# sinclair_keyboard_v2.net
KiCad netlist of a schematic drawn in EAGLE
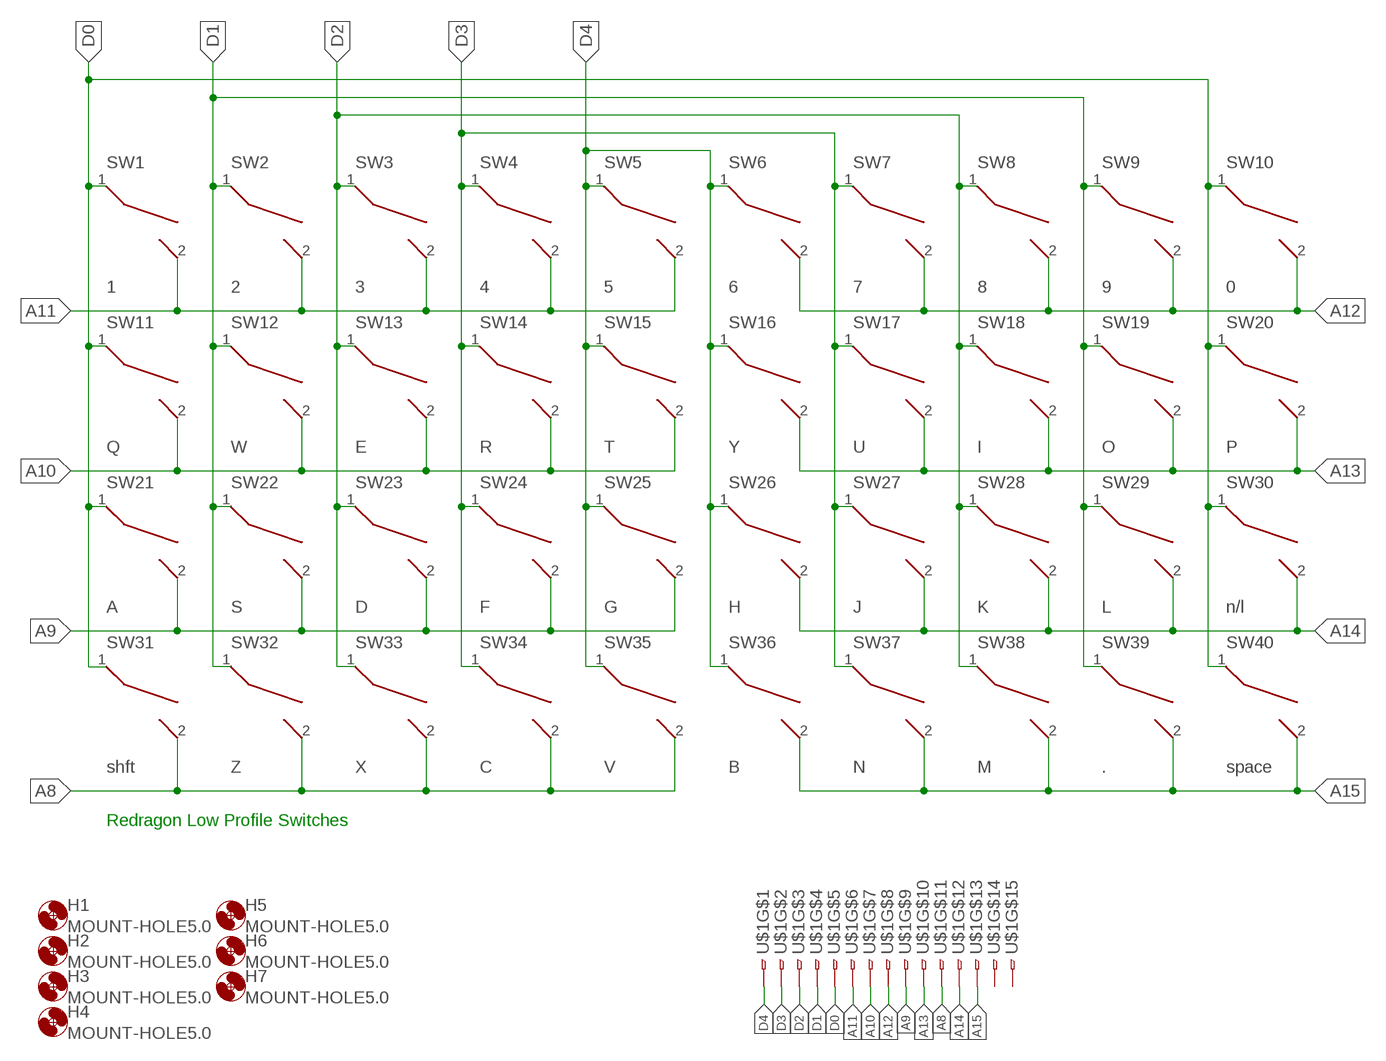
[diagram p0: schematic, sheet 1]

(export (version "E")
  (design (tool "Eeschema 10.0.6"))
  (components
    (comp (ref "H1")
      (value "MOUNT-HOLE5.0")
      (footprint "eagle-import:5,0")
      (libsource (lib "eagle-import") (part "MOUNT-HOLE5.0"))
    )
    (comp (ref "H2")
      (value "MOUNT-HOLE5.0")
      (footprint "eagle-import:5,0")
      (libsource (lib "eagle-import") (part "MOUNT-HOLE5.0"))
    )
    (comp (ref "H3")
      (value "MOUNT-HOLE5.0")
      (footprint "eagle-import:5,0")
      (libsource (lib "eagle-import") (part "MOUNT-HOLE5.0"))
    )
    (comp (ref "H4")
      (value "MOUNT-HOLE5.0")
      (footprint "eagle-import:5,0")
      (libsource (lib "eagle-import") (part "MOUNT-HOLE5.0"))
    )
    (comp (ref "H5")
      (value "MOUNT-HOLE5.0")
      (footprint "eagle-import:5,0")
      (libsource (lib "eagle-import") (part "MOUNT-HOLE5.0"))
    )
    (comp (ref "H6")
      (value "MOUNT-HOLE5.0")
      (footprint "eagle-import:5,0")
      (libsource (lib "eagle-import") (part "MOUNT-HOLE5.0"))
    )
    (comp (ref "H7")
      (value "MOUNT-HOLE5.0")
      (footprint "eagle-import:5,0")
      (libsource (lib "eagle-import") (part "MOUNT-HOLE5.0"))
    )
    (comp (ref "SW1")
      (value "1")
      (footprint "eagle-import:REDRAGON_LOWPROFILE")
      (libsource (lib "eagle-import") (part "CHERRY_MXREDRAGON"))
    )
    (comp (ref "SW2")
      (value "2")
      (footprint "eagle-import:REDRAGON_LOWPROFILE")
      (libsource (lib "eagle-import") (part "CHERRY_MXREDRAGON"))
    )
    (comp (ref "SW3")
      (value "3")
      (footprint "eagle-import:REDRAGON_LOWPROFILE")
      (libsource (lib "eagle-import") (part "CHERRY_MXREDRAGON"))
    )
    (comp (ref "SW4")
      (value "4")
      (footprint "eagle-import:REDRAGON_LOWPROFILE")
      (libsource (lib "eagle-import") (part "CHERRY_MXREDRAGON"))
    )
    (comp (ref "SW5")
      (value "5")
      (footprint "eagle-import:REDRAGON_LOWPROFILE")
      (libsource (lib "eagle-import") (part "CHERRY_MXREDRAGON"))
    )
    (comp (ref "SW6")
      (value "6")
      (footprint "eagle-import:REDRAGON_LOWPROFILE")
      (libsource (lib "eagle-import") (part "CHERRY_MXREDRAGON"))
    )
    (comp (ref "SW7")
      (value "7")
      (footprint "eagle-import:REDRAGON_LOWPROFILE")
      (libsource (lib "eagle-import") (part "CHERRY_MXREDRAGON"))
    )
    (comp (ref "SW8")
      (value "8")
      (footprint "eagle-import:REDRAGON_LOWPROFILE")
      (libsource (lib "eagle-import") (part "CHERRY_MXREDRAGON"))
    )
    (comp (ref "SW9")
      (value "9")
      (footprint "eagle-import:REDRAGON_LOWPROFILE")
      (libsource (lib "eagle-import") (part "CHERRY_MXREDRAGON"))
    )
    (comp (ref "SW10")
      (value "0")
      (footprint "eagle-import:REDRAGON_LOWPROFILE")
      (libsource (lib "eagle-import") (part "CHERRY_MXREDRAGON"))
    )
    (comp (ref "SW11")
      (value "Q")
      (footprint "eagle-import:REDRAGON_LOWPROFILE")
      (libsource (lib "eagle-import") (part "CHERRY_MXREDRAGON"))
    )
    (comp (ref "SW12")
      (value "W")
      (footprint "eagle-import:REDRAGON_LOWPROFILE")
      (libsource (lib "eagle-import") (part "CHERRY_MXREDRAGON"))
    )
    (comp (ref "SW13")
      (value "E")
      (footprint "eagle-import:REDRAGON_LOWPROFILE")
      (libsource (lib "eagle-import") (part "CHERRY_MXREDRAGON"))
    )
    (comp (ref "SW14")
      (value "R")
      (footprint "eagle-import:REDRAGON_LOWPROFILE")
      (libsource (lib "eagle-import") (part "CHERRY_MXREDRAGON"))
    )
    (comp (ref "SW15")
      (value "T")
      (footprint "eagle-import:REDRAGON_LOWPROFILE")
      (libsource (lib "eagle-import") (part "CHERRY_MXREDRAGON"))
    )
    (comp (ref "SW16")
      (value "Y")
      (footprint "eagle-import:REDRAGON_LOWPROFILE")
      (libsource (lib "eagle-import") (part "CHERRY_MXREDRAGON"))
    )
    (comp (ref "SW17")
      (value "U")
      (footprint "eagle-import:REDRAGON_LOWPROFILE")
      (libsource (lib "eagle-import") (part "CHERRY_MXREDRAGON"))
    )
    (comp (ref "SW18")
      (value "I")
      (footprint "eagle-import:REDRAGON_LOWPROFILE")
      (libsource (lib "eagle-import") (part "CHERRY_MXREDRAGON"))
    )
    (comp (ref "SW19")
      (value "O")
      (footprint "eagle-import:REDRAGON_LOWPROFILE")
      (libsource (lib "eagle-import") (part "CHERRY_MXREDRAGON"))
    )
    (comp (ref "SW20")
      (value "P")
      (footprint "eagle-import:REDRAGON_LOWPROFILE")
      (libsource (lib "eagle-import") (part "CHERRY_MXREDRAGON"))
    )
    (comp (ref "SW21")
      (value "A")
      (footprint "eagle-import:REDRAGON_LOWPROFILE")
      (libsource (lib "eagle-import") (part "CHERRY_MXREDRAGON"))
    )
    (comp (ref "SW22")
      (value "S")
      (footprint "eagle-import:REDRAGON_LOWPROFILE")
      (libsource (lib "eagle-import") (part "CHERRY_MXREDRAGON"))
    )
    (comp (ref "SW23")
      (value "D")
      (footprint "eagle-import:REDRAGON_LOWPROFILE")
      (libsource (lib "eagle-import") (part "CHERRY_MXREDRAGON"))
    )
    (comp (ref "SW24")
      (value "F")
      (footprint "eagle-import:REDRAGON_LOWPROFILE")
      (libsource (lib "eagle-import") (part "CHERRY_MXREDRAGON"))
    )
    (comp (ref "SW25")
      (value "G")
      (footprint "eagle-import:REDRAGON_LOWPROFILE")
      (libsource (lib "eagle-import") (part "CHERRY_MXREDRAGON"))
    )
    (comp (ref "SW26")
      (value "H")
      (footprint "eagle-import:REDRAGON_LOWPROFILE")
      (libsource (lib "eagle-import") (part "CHERRY_MXREDRAGON"))
    )
    (comp (ref "SW27")
      (value "J")
      (footprint "eagle-import:REDRAGON_LOWPROFILE")
      (libsource (lib "eagle-import") (part "CHERRY_MXREDRAGON"))
    )
    (comp (ref "SW28")
      (value "K")
      (footprint "eagle-import:REDRAGON_LOWPROFILE")
      (libsource (lib "eagle-import") (part "CHERRY_MXREDRAGON"))
    )
    (comp (ref "SW29")
      (value "L")
      (footprint "eagle-import:REDRAGON_LOWPROFILE")
      (libsource (lib "eagle-import") (part "CHERRY_MXREDRAGON"))
    )
    (comp (ref "SW30")
      (value "n/l")
      (footprint "eagle-import:REDRAGON_LOWPROFILE")
      (libsource (lib "eagle-import") (part "CHERRY_MXREDRAGON"))
    )
    (comp (ref "SW31")
      (value "shft")
      (footprint "eagle-import:REDRAGON_LOWPROFILE")
      (libsource (lib "eagle-import") (part "CHERRY_MXREDRAGON"))
    )
    (comp (ref "SW32")
      (value "Z")
      (footprint "eagle-import:REDRAGON_LOWPROFILE")
      (libsource (lib "eagle-import") (part "CHERRY_MXREDRAGON"))
    )
    (comp (ref "SW33")
      (value "X")
      (footprint "eagle-import:REDRAGON_LOWPROFILE")
      (libsource (lib "eagle-import") (part "CHERRY_MXREDRAGON"))
    )
    (comp (ref "SW34")
      (value "C")
      (footprint "eagle-import:REDRAGON_LOWPROFILE")
      (libsource (lib "eagle-import") (part "CHERRY_MXREDRAGON"))
    )
    (comp (ref "SW35")
      (value "V")
      (footprint "eagle-import:REDRAGON_LOWPROFILE")
      (libsource (lib "eagle-import") (part "CHERRY_MXREDRAGON"))
    )
    (comp (ref "SW36")
      (value "B")
      (footprint "eagle-import:REDRAGON_LOWPROFILE")
      (libsource (lib "eagle-import") (part "CHERRY_MXREDRAGON"))
    )
    (comp (ref "SW37")
      (value "N")
      (footprint "eagle-import:REDRAGON_LOWPROFILE")
      (libsource (lib "eagle-import") (part "CHERRY_MXREDRAGON"))
    )
    (comp (ref "SW38")
      (value "M")
      (footprint "eagle-import:REDRAGON_LOWPROFILE")
      (libsource (lib "eagle-import") (part "CHERRY_MXREDRAGON"))
    )
    (comp (ref "SW39")
      (value ".")
      (footprint "eagle-import:REDRAGON_LOWPROFILE")
      (libsource (lib "eagle-import") (part "CHERRY_MXREDRAGON"))
    )
    (comp (ref "SW40")
      (value "space")
      (footprint "eagle-import:REDRAGON_LOWPROFILE")
      (libsource (lib "eagle-import") (part "CHERRY_MXREDRAGON"))
    )
    (comp (ref "U$1")
      (value "FH12-15S-1SH")
      (footprint "eagle-import:FH12-15S-1SH")
      (libsource (lib "eagle-import") (part "FH12-15S-1SH"))
    )
  )
  (nets
    (net (code "1") (name "A8") (class "Default")
      (node (ref "SW31") (pin "2") (pinfunction "2_2") (pintype "passive"))
      (node (ref "SW32") (pin "2") (pinfunction "2_2") (pintype "passive"))
      (node (ref "SW33") (pin "2") (pinfunction "2_2") (pintype "passive"))
      (node (ref "SW34") (pin "2") (pinfunction "2_2") (pintype "passive"))
      (node (ref "SW35") (pin "2") (pinfunction "2_2") (pintype "passive"))
      (node (ref "U$1") (pin "11") (pinfunction "1_11") (pintype "passive"))
    )
    (net (code "2") (name "A9") (class "Default")
      (node (ref "SW21") (pin "2") (pinfunction "2_2") (pintype "passive"))
      (node (ref "SW22") (pin "2") (pinfunction "2_2") (pintype "passive"))
      (node (ref "SW23") (pin "2") (pinfunction "2_2") (pintype "passive"))
      (node (ref "SW24") (pin "2") (pinfunction "2_2") (pintype "passive"))
      (node (ref "SW25") (pin "2") (pinfunction "2_2") (pintype "passive"))
      (node (ref "U$1") (pin "9") (pinfunction "1_9") (pintype "passive"))
    )
    (net (code "3") (name "A10") (class "Default")
      (node (ref "SW11") (pin "2") (pinfunction "2_2") (pintype "passive"))
      (node (ref "SW12") (pin "2") (pinfunction "2_2") (pintype "passive"))
      (node (ref "SW13") (pin "2") (pinfunction "2_2") (pintype "passive"))
      (node (ref "SW14") (pin "2") (pinfunction "2_2") (pintype "passive"))
      (node (ref "SW15") (pin "2") (pinfunction "2_2") (pintype "passive"))
      (node (ref "U$1") (pin "7") (pinfunction "1_7") (pintype "passive"))
    )
    (net (code "4") (name "A11") (class "Default")
      (node (ref "SW1") (pin "2") (pinfunction "2_2") (pintype "passive"))
      (node (ref "SW2") (pin "2") (pinfunction "2_2") (pintype "passive"))
      (node (ref "SW3") (pin "2") (pinfunction "2_2") (pintype "passive"))
      (node (ref "SW4") (pin "2") (pinfunction "2_2") (pintype "passive"))
      (node (ref "SW5") (pin "2") (pinfunction "2_2") (pintype "passive"))
      (node (ref "U$1") (pin "6") (pinfunction "1_6") (pintype "passive"))
    )
    (net (code "5") (name "A12") (class "Default")
      (node (ref "SW10") (pin "2") (pinfunction "2_2") (pintype "passive"))
      (node (ref "SW6") (pin "2") (pinfunction "2_2") (pintype "passive"))
      (node (ref "SW7") (pin "2") (pinfunction "2_2") (pintype "passive"))
      (node (ref "SW8") (pin "2") (pinfunction "2_2") (pintype "passive"))
      (node (ref "SW9") (pin "2") (pinfunction "2_2") (pintype "passive"))
      (node (ref "U$1") (pin "8") (pinfunction "1_8") (pintype "passive"))
    )
    (net (code "6") (name "A13") (class "Default")
      (node (ref "SW16") (pin "2") (pinfunction "2_2") (pintype "passive"))
      (node (ref "SW17") (pin "2") (pinfunction "2_2") (pintype "passive"))
      (node (ref "SW18") (pin "2") (pinfunction "2_2") (pintype "passive"))
      (node (ref "SW19") (pin "2") (pinfunction "2_2") (pintype "passive"))
      (node (ref "SW20") (pin "2") (pinfunction "2_2") (pintype "passive"))
      (node (ref "U$1") (pin "10") (pinfunction "1_10") (pintype "passive"))
    )
    (net (code "7") (name "A14") (class "Default")
      (node (ref "SW26") (pin "2") (pinfunction "2_2") (pintype "passive"))
      (node (ref "SW27") (pin "2") (pinfunction "2_2") (pintype "passive"))
      (node (ref "SW28") (pin "2") (pinfunction "2_2") (pintype "passive"))
      (node (ref "SW29") (pin "2") (pinfunction "2_2") (pintype "passive"))
      (node (ref "SW30") (pin "2") (pinfunction "2_2") (pintype "passive"))
      (node (ref "U$1") (pin "12") (pinfunction "1_12") (pintype "passive"))
    )
    (net (code "8") (name "A15") (class "Default")
      (node (ref "SW36") (pin "2") (pinfunction "2_2") (pintype "passive"))
      (node (ref "SW37") (pin "2") (pinfunction "2_2") (pintype "passive"))
      (node (ref "SW38") (pin "2") (pinfunction "2_2") (pintype "passive"))
      (node (ref "SW39") (pin "2") (pinfunction "2_2") (pintype "passive"))
      (node (ref "SW40") (pin "2") (pinfunction "2_2") (pintype "passive"))
      (node (ref "U$1") (pin "13") (pinfunction "1_13") (pintype "passive"))
    )
    (net (code "9") (name "D0") (class "Default")
      (node (ref "SW1") (pin "1") (pinfunction "1_1") (pintype "passive"))
      (node (ref "SW10") (pin "1") (pinfunction "1_1") (pintype "passive"))
      (node (ref "SW11") (pin "1") (pinfunction "1_1") (pintype "passive"))
      (node (ref "SW20") (pin "1") (pinfunction "1_1") (pintype "passive"))
      (node (ref "SW21") (pin "1") (pinfunction "1_1") (pintype "passive"))
      (node (ref "SW30") (pin "1") (pinfunction "1_1") (pintype "passive"))
      (node (ref "SW31") (pin "1") (pinfunction "1_1") (pintype "passive"))
      (node (ref "SW40") (pin "1") (pinfunction "1_1") (pintype "passive"))
      (node (ref "U$1") (pin "5") (pinfunction "1_5") (pintype "passive"))
    )
    (net (code "10") (name "D1") (class "Default")
      (node (ref "SW12") (pin "1") (pinfunction "1_1") (pintype "passive"))
      (node (ref "SW19") (pin "1") (pinfunction "1_1") (pintype "passive"))
      (node (ref "SW2") (pin "1") (pinfunction "1_1") (pintype "passive"))
      (node (ref "SW22") (pin "1") (pinfunction "1_1") (pintype "passive"))
      (node (ref "SW29") (pin "1") (pinfunction "1_1") (pintype "passive"))
      (node (ref "SW32") (pin "1") (pinfunction "1_1") (pintype "passive"))
      (node (ref "SW39") (pin "1") (pinfunction "1_1") (pintype "passive"))
      (node (ref "SW9") (pin "1") (pinfunction "1_1") (pintype "passive"))
      (node (ref "U$1") (pin "4") (pinfunction "1_4") (pintype "passive"))
    )
    (net (code "11") (name "D2") (class "Default")
      (node (ref "SW13") (pin "1") (pinfunction "1_1") (pintype "passive"))
      (node (ref "SW18") (pin "1") (pinfunction "1_1") (pintype "passive"))
      (node (ref "SW23") (pin "1") (pinfunction "1_1") (pintype "passive"))
      (node (ref "SW28") (pin "1") (pinfunction "1_1") (pintype "passive"))
      (node (ref "SW3") (pin "1") (pinfunction "1_1") (pintype "passive"))
      (node (ref "SW33") (pin "1") (pinfunction "1_1") (pintype "passive"))
      (node (ref "SW38") (pin "1") (pinfunction "1_1") (pintype "passive"))
      (node (ref "SW8") (pin "1") (pinfunction "1_1") (pintype "passive"))
      (node (ref "U$1") (pin "3") (pinfunction "1_3") (pintype "passive"))
    )
    (net (code "12") (name "D3") (class "Default")
      (node (ref "SW14") (pin "1") (pinfunction "1_1") (pintype "passive"))
      (node (ref "SW17") (pin "1") (pinfunction "1_1") (pintype "passive"))
      (node (ref "SW24") (pin "1") (pinfunction "1_1") (pintype "passive"))
      (node (ref "SW27") (pin "1") (pinfunction "1_1") (pintype "passive"))
      (node (ref "SW34") (pin "1") (pinfunction "1_1") (pintype "passive"))
      (node (ref "SW37") (pin "1") (pinfunction "1_1") (pintype "passive"))
      (node (ref "SW4") (pin "1") (pinfunction "1_1") (pintype "passive"))
      (node (ref "SW7") (pin "1") (pinfunction "1_1") (pintype "passive"))
      (node (ref "U$1") (pin "2") (pinfunction "1_2") (pintype "passive"))
    )
    (net (code "13") (name "D4") (class "Default")
      (node (ref "SW15") (pin "1") (pinfunction "1_1") (pintype "passive"))
      (node (ref "SW16") (pin "1") (pinfunction "1_1") (pintype "passive"))
      (node (ref "SW25") (pin "1") (pinfunction "1_1") (pintype "passive"))
      (node (ref "SW26") (pin "1") (pinfunction "1_1") (pintype "passive"))
      (node (ref "SW35") (pin "1") (pinfunction "1_1") (pintype "passive"))
      (node (ref "SW36") (pin "1") (pinfunction "1_1") (pintype "passive"))
      (node (ref "SW5") (pin "1") (pinfunction "1_1") (pintype "passive"))
      (node (ref "SW6") (pin "1") (pinfunction "1_1") (pintype "passive"))
      (node (ref "U$1") (pin "1") (pinfunction "1_1") (pintype "passive"))
    )
    (net (code "14") (name "unconnected-(U$1F-1-Pad14)") (class "Default")
      (node (ref "U$1") (pin "14") (pinfunction "1_14") (pintype "passive"))
    )
    (net (code "15") (name "unconnected-(U$1G-1-Pad15)") (class "Default")
      (node (ref "U$1") (pin "15") (pinfunction "1_15") (pintype "passive"))
    )
  )
)
